# tgs2611-c00-v2_brd.net
KiCad netlist of a schematic drawn in EAGLE
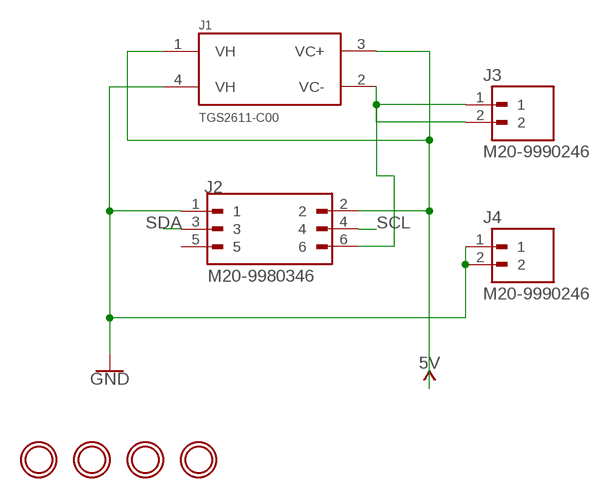
[diagram p0: schematic, sheet 1]

(export (version "E")
  (design (tool "Eeschema 10.0.6"))
  (components
    (comp (ref "J1")
      (value "TGS2611-C00")
      (footprint "eagle-import:TO180P920X780-4P")
      (fields (field (name "MF") "Figaro"))
      (libsource (lib "eagle-import") (part "TGS2611-C00"))
    )
    (comp (ref "J2")
      (value "M20-9980346")
      (footprint "eagle-import:HARWIN_M20-9980346")
      (fields (field (name "MANUFACTURER") "HARWIN"))
      (libsource (lib "eagle-import") (part "M20-9980346"))
    )
    (comp (ref "J3")
      (value "M20-9990246")
      (footprint "eagle-import:HARWIN_M20-9990246")
      (fields (field (name "MANUFACTURER") "Harwin"))
      (libsource (lib "eagle-import") (part "M20-9990246"))
    )
    (comp (ref "J4")
      (value "M20-9990246")
      (footprint "eagle-import:HARWIN_M20-9990246")
      (fields (field (name "MANUFACTURER") "Harwin"))
      (libsource (lib "eagle-import") (part "M20-9990246"))
    )
    (comp (ref "U$1")
      (value "MOUNTINGHOLE2.5")
      (footprint "eagle-import:MOUNTINGHOLE_2.5_PLATED")
      (libsource (lib "eagle-import") (part "MOUNTINGHOLE2.5"))
    )
    (comp (ref "U$2")
      (value "MOUNTINGHOLE2.5")
      (footprint "eagle-import:MOUNTINGHOLE_2.5_PLATED")
      (libsource (lib "eagle-import") (part "MOUNTINGHOLE2.5"))
    )
    (comp (ref "U$3")
      (value "MOUNTINGHOLE2.5")
      (footprint "eagle-import:MOUNTINGHOLE_2.5_PLATED")
      (libsource (lib "eagle-import") (part "MOUNTINGHOLE2.5"))
    )
    (comp (ref "U$4")
      (value "MOUNTINGHOLE2.5")
      (footprint "eagle-import:MOUNTINGHOLE_2.5_PLATED")
      (libsource (lib "eagle-import") (part "MOUNTINGHOLE2.5"))
    )
  )
  (nets
    (net (code "1") (name "/SCL") (class "Default")
      (node (ref "J2") (pin "4") (pinfunction "4_4") (pintype "passive"))
    )
    (net (code "2") (name "/SDA") (class "Default")
      (node (ref "J2") (pin "3") (pinfunction "3_3") (pintype "passive"))
    )
    (net (code "3") (name "5V") (class "Default")
      (node (ref "J1") (pin "1") (pinfunction "VH_1") (pintype "input"))
      (node (ref "J1") (pin "3") (pinfunction "VC+_3") (pintype "power_in"))
      (node (ref "J2") (pin "2") (pinfunction "2_2") (pintype "passive"))
    )
    (net (code "4") (name "GND") (class "Default")
      (node (ref "J1") (pin "4") (pinfunction "VH_4") (pintype "input"))
      (node (ref "J2") (pin "1") (pinfunction "1_1") (pintype "passive"))
      (node (ref "J4") (pin "1") (pinfunction "1_1") (pintype "passive"))
      (node (ref "J4") (pin "2") (pinfunction "2_2") (pintype "passive"))
    )
    (net (code "5") (name "Net-(J1-VC-)") (class "Default")
      (node (ref "J1") (pin "2") (pinfunction "VC-_2") (pintype "power_in"))
      (node (ref "J2") (pin "6") (pinfunction "6_6") (pintype "passive"))
      (node (ref "J3") (pin "1") (pinfunction "1_1") (pintype "passive"))
      (node (ref "J3") (pin "2") (pinfunction "2_2") (pintype "passive"))
    )
    (net (code "6") (name "unconnected-(J2-Pad5)") (class "Default")
      (node (ref "J2") (pin "5") (pinfunction "5_5") (pintype "passive"))
    )
  )
)
